# 11.net
KiCad netlist of a schematic drawn in Altium Designer
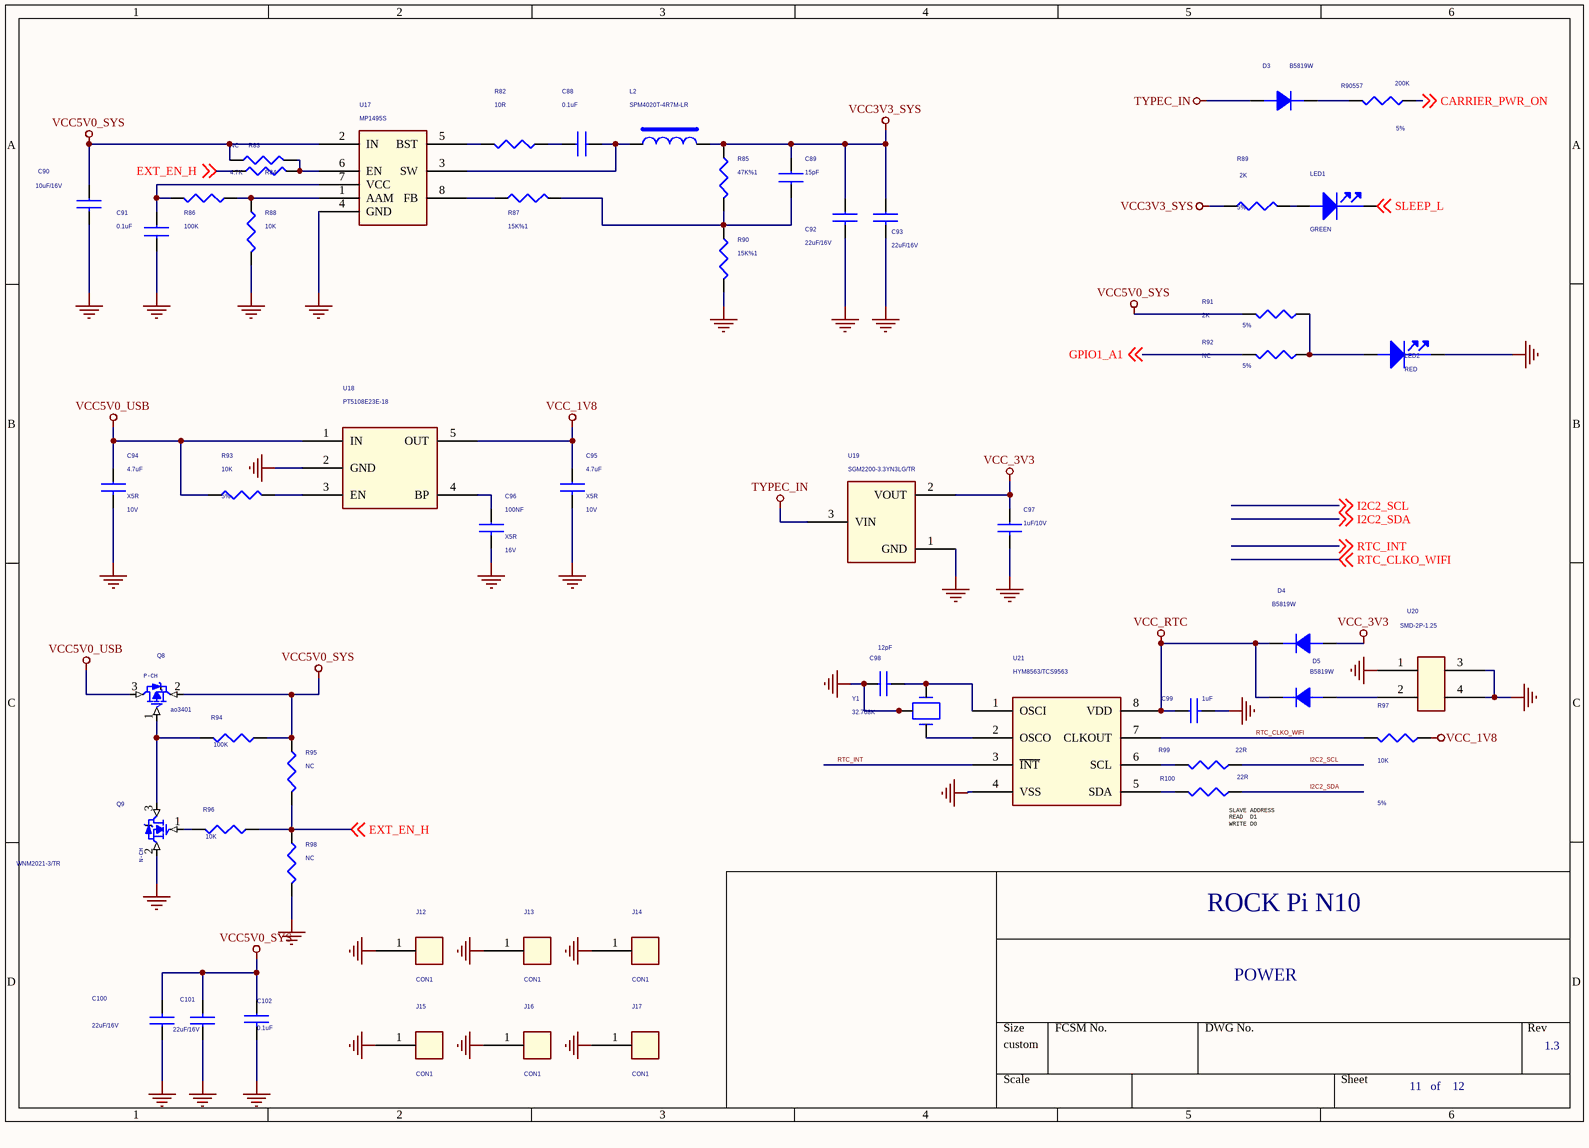
[diagram p0: 11.SchDoc]

(export (version "E")
  (design (tool "Eeschema 10.0.6"))
  (components
    (comp (ref "C88")
      (value "0.1uF")
      (footprint "C0603")
      (description "RoHS CHIP CAP 1uF +10/-10% 16V X5R")
      (libsource (lib "*") (part "CAP NP_Dup3"))
    )
    (comp (ref "C89")
      (value "15pF")
      (footprint "C0603")
      (description "RoHS CHIP CAP 1uF +10/-10% 16V X5R")
      (libsource (lib "*") (part "CAP NP_Dup3"))
    )
    (comp (ref "C90") (value "10uF/16V") (footprint "C0603") (libsource (lib "*") (part "CAP NP_2_Dup1")))
    (comp (ref "C91")
      (value "0.1uF")
      (footprint "C0603")
      (description "RoHS CHIP CAP 1uF +10/-10% 16V X5R")
      (libsource (lib "*") (part "CAP NP_Dup3"))
    )
    (comp (ref "C92") (value "22uF/16V") (footprint "C0805") (libsource (lib "*") (part "CAP NP_2_Dup1")))
    (comp (ref "C93") (value "22uF/16V") (footprint "C0805") (libsource (lib "*") (part "CAP NP_2_Dup1")))
    (comp (ref "C94")
      (value "4.7uF")
      (footprint "C0603")
      (description "cap,4.70uF,+/-10%,10V,X5R,C0603")
      (fields
        (field (name "DIELECTRIC") "X5R")
        (field (name "VOLTAGE") "10V")
        (field (name "MANUFACTURER") "TDK")
        (field (name "TOLERANCE") "10%")
        (field (name "CREATED BY") "JJJ")
      )
      (libsource (lib "*") (part "CAP NP_2"))
    )
    (comp (ref "C95")
      (value "4.7uF")
      (footprint "C0603")
      (description "cap,4.70uF,+/-10%,10V,X5R,C0603")
      (fields
        (field (name "DIELECTRIC") "X5R")
        (field (name "VOLTAGE") "10V")
        (field (name "TOLERANCE") "10%")
        (field (name "MANUFACTURER") "TDK")
        (field (name "CREATED BY") "JJJ")
      )
      (libsource (lib "*") (part "CAP NP_2"))
    )
    (comp (ref "C96")
      (value "100NF")
      (footprint "C0402")
      (description "cap,100.00nF,+/-10%,16V,X5R,C0402")
      (fields
        (field (name "DIELECTRIC") "X5R")
        (field (name "VOLTAGE") "16V")
        (field (name "MANUFACTURER") "TDK")
        (field (name "TOLERANCE") "10%")
        (field (name "CREATED BY") "JJJ")
      )
      (libsource (lib "*") (part "CAP NP_2"))
    )
    (comp (ref "C97")
      (value "1uF/10V")
      (footprint "C0402")
      (description "RoHS CHIP CAP 1uF +10/-10% X5R")
      (libsource (lib "*") (part "CAP NP_Dup1"))
    )
    (comp (ref "C98")
      (value "12pF")
      (footprint "C0402")
      (description "CAP,MLCC,8pF,+/-0.5pF,NPO,6.3V,SMD0402")
      (libsource (lib "*") (part "CAP NP_Dup1"))
    )
    (comp (ref "C99")
      (value "1uF")
      (footprint "C0402")
      (description "RoHS CHIP CAP 1uF +10/-10% X5R")
      (libsource (lib "*") (part "CAP NP_Dup2"))
    )
    (comp (ref "C100") (value "22uF/16V") (footprint "C0805") (libsource (lib "*") (part "CAP NP_4")))
    (comp (ref "C101") (value "22uF/16V") (footprint "C0805") (libsource (lib "*") (part "CAP NP_4")))
    (comp (ref "C102")
      (value "0.1uF")
      (footprint "C0402")
      (description "CAP,MLCC,1nF,+/-10%,X5R,6.3V,SMD0402")
      (libsource (lib "*") (part "CAP NP_Dup1"))
    )
    (comp (ref "D3")
      (value "B5819W")
      (footprint "SOD_123")
      (description "Schottky Barrier，B5819W SOD-123")
      (fields (field (name "MANUFACTURER") "长电") (field (name "CREATED BY") "JJJ"))
      (libsource (lib "*") (part "DIODE"))
    )
    (comp (ref "D4")
      (value "B5819W")
      (footprint "SOD_123")
      (description "Schottky Barrier，B5819W SOD-123")
      (fields (field (name "MANUFACTURER") "长电") (field (name "CREATED BY") "JJJ"))
      (libsource (lib "*") (part "DIODE"))
    )
    (comp (ref "D5")
      (value "B5819W")
      (footprint "SOD_123")
      (description "Schottky Barrier，B5819W SOD-123")
      (fields (field (name "MANUFACTURER") "长电") (field (name "CREATED BY") "JJJ"))
      (libsource (lib "*") (part "DIODE"))
    )
    (comp (ref "J12") (value "CON1") (footprint "H3.8MM") (libsource (lib "*") (part "CON1")))
    (comp (ref "J13") (value "CON1") (footprint "H3.8MM") (libsource (lib "*") (part "CON1")))
    (comp (ref "J14") (value "CON1") (footprint "H3.8MM") (libsource (lib "*") (part "CON1")))
    (comp (ref "J15") (value "CON1") (footprint "H3.8MM") (libsource (lib "*") (part "CON1")))
    (comp (ref "J16") (value "CON1") (footprint "H2.8MM") (libsource (lib "*") (part "CON1")))
    (comp (ref "J17") (value "CON1") (footprint "H2.8MM") (libsource (lib "*") (part "CON1")))
    (comp (ref "L2")
      (value "SPM4020T-4R7M-LR")
      (footprint "IND-4X4")
      (libsource (lib "*") (part "INDUCTORS OF FERRITE_Dup1"))
    )
    (comp (ref "LED1") (value "GREEN") (footprint "LED0603") (libsource (lib "*") (part "LED_0")))
    (comp (ref "LED2")
      (value "RED")
      (footprint "LED0603")
      (description "贴片LED灯，0603，绿色")
      (fields (field (name "CREATED BY") "JJJ"))
      (libsource (lib "*") (part "LED"))
    )
    (comp (ref "Q8") (value "ao3401") (footprint "S0T-23") (libsource (lib "*") (part "P-MOSFET")))
    (comp (ref "Q9") (value "WNM2021-3/TR") (footprint "S0T-23") (libsource (lib "*") (part "N-MOSFET")))
    (comp (ref "R82")
      (value "10R")
      (footprint "R0402")
      (description "RES,thick film,47KOhm,+/-5%,1/16W,SMD0402")
      (libsource (lib "*") (part "RESISTOR_0"))
    )
    (comp (ref "R83")
      (value "NC")
      (footprint "R0402")
      (description "RES,thick film,47KOhm,+/-5%,1/16W,SMD0402")
      (libsource (lib "*") (part "RESISTOR_0"))
    )
    (comp (ref "R84")
      (value "4.7K")
      (footprint "R0402")
      (description "RES,thick film,47KOhm,+/-5%,1/16W,SMD0402")
      (libsource (lib "*") (part "RESISTOR_0"))
    )
    (comp (ref "R85")
      (value "47K%1")
      (footprint "R0402")
      (description "RES,thick film,47KOhm,+/-5%,1/16W,SMD0402")
      (libsource (lib "*") (part "RESISTOR_0"))
    )
    (comp (ref "R86")
      (value "100K")
      (footprint "R0402")
      (description "RES,thick film,47KOhm,+/-5%,1/16W,SMD0402")
      (libsource (lib "*") (part "RESISTOR_0"))
    )
    (comp (ref "R87")
      (value "15K%1")
      (footprint "R0402")
      (description "RES,thick film,47KOhm,+/-5%,1/16W,SMD0402")
      (libsource (lib "*") (part "RESISTOR_0"))
    )
    (comp (ref "R88")
      (value "10K")
      (footprint "R0402")
      (description "RES,thick film,47KOhm,+/-5%,1/16W,SMD0402")
      (libsource (lib "*") (part "RESISTOR_0"))
    )
    (comp (ref "R89")
      (value "2K")
      (footprint "R0402")
      (description "通用厚膜电阻,10K,+/-5%,R0402,1/16W.")
      (fields
        (field (name "TOLERANCE") "5%")
        (field (name "MANUFACTURER") "YAGEO")
        (field (name "CREATED BY") "YTL")
      )
      (libsource (lib "*") (part "RESISTOR_3"))
    )
    (comp (ref "R90")
      (value "15K%1")
      (footprint "R0402")
      (description "RES,thick film,47KOhm,+/-5%,1/16W,SMD0402")
      (libsource (lib "*") (part "RESISTOR_0"))
    )
    (comp (ref "R91")
      (value "2K")
      (footprint "R0402")
      (description "通用厚膜电阻,330R,+/-5%,R0402,1/16W.")
      (fields
        (field (name "TOLERANCE") "5%")
        (field (name "MANUFACTURER") "YAGEO")
        (field (name "CREATED BY") "YTL")
      )
      (libsource (lib "*") (part "RESISTOR_3"))
    )
    (comp (ref "R92")
      (value "NC")
      (footprint "R0402")
      (description "通用厚膜电阻,330R,+/-5%,R0402,1/16W.")
      (fields
        (field (name "TOLERANCE") "5%")
        (field (name "MANUFACTURER") "YAGEO")
        (field (name "CREATED BY") "YTL")
      )
      (libsource (lib "*") (part "RESISTOR_3"))
    )
    (comp (ref "R93")
      (value "10K")
      (footprint "R0402")
      (description "通用厚膜电阻,10K,+/-5%,R0402,1/16W.")
      (fields
        (field (name "TOLERANCE") "5%")
        (field (name "MANUFACTURER") "YAGEO")
        (field (name "CREATED BY") "YTL")
      )
      (libsource (lib "*") (part "RESISTOR_3"))
    )
    (comp (ref "R94")
      (value "100K")
      (footprint "R0402")
      (description "RES,thick film,47KOhm,+/-5%,1/16W,SMD0402")
      (libsource (lib "*") (part "RESISTOR_1"))
    )
    (comp (ref "R95")
      (value "NC")
      (footprint "R0402")
      (description "RES,thick film,47KOhm,+/-5%,1/16W,SMD0402")
      (libsource (lib "*") (part "RESISTOR_0"))
    )
    (comp (ref "R96")
      (value "10K")
      (footprint "R0402")
      (description "RES,thick film,47KOhm,+/-5%,1/16W,SMD0402")
      (libsource (lib "*") (part "RESISTOR_1"))
    )
    (comp (ref "R97")
      (value "10K")
      (footprint "R0402")
      (description "通用厚膜电阻,5K1,+/-5%,R0402,1/16W.")
      (fields
        (field (name "TOLERANCE") "5%")
        (field (name "MANUFACTURER") "YAGEO")
        (field (name "CREATED BY") "YTL")
      )
      (libsource (lib "*") (part "RESISTOR_3"))
    )
    (comp (ref "R98")
      (value "NC")
      (footprint "R0402")
      (description "RES,thick film,47KOhm,+/-5%,1/16W,SMD0402")
      (libsource (lib "*") (part "RESISTOR_0"))
    )
    (comp (ref "R99")
      (value "22R")
      (footprint "R0402")
      (description "通用厚膜电阻,5K1,+/-5%,R0402,1/16W.")
      (fields
        (field (name "TOLERANCE") "5%")
        (field (name "MANUFACTURER") "YAGEO")
        (field (name "CREATED BY") "YTL")
      )
      (libsource (lib "*") (part "RESISTOR_3"))
    )
    (comp (ref "R100")
      (value "22R")
      (footprint "R0402")
      (description "通用厚膜电阻,5K1,+/-5%,R0402,1/16W.")
      (fields
        (field (name "TOLERANCE") "5%")
        (field (name "MANUFACTURER") "YAGEO")
        (field (name "CREATED BY") "YTL")
      )
      (libsource (lib "*") (part "RESISTOR_3"))
    )
    (comp (ref "R90557")
      (value "200K")
      (footprint "R0402")
      (description "通用厚膜电阻,330R,+/-5%,R0402,1/16W.")
      (fields
        (field (name "TOLERANCE") "5%")
        (field (name "MANUFACTURER") "YAGEO")
        (field (name "CREATED BY") "YTL")
      )
      (libsource (lib "*") (part "RESISTOR_3"))
    )
    (comp (ref "U17") (value "MP1495S") (footprint "TSOT_23_8") (libsource (lib "*") (part "BUCK-MP1495")))
    (comp (ref "U18")
      (value "PT5108E23E-18")
      (footprint "SOT25")
      (description "500mA, Low Dropout, Low Noise Ultra-Fast Without Bypass Capacitor CMOS LDO Regulator")
      (fields (field (name "MANUFACTURER") "Richtek（立錡）") (field (name "CREATED BY") "JJJ"))
      (libsource (lib "*") (part "LDO_PT5108"))
    )
    (comp (ref "U19")
      (value "SGM2200-3.3YN3LG/TR")
      (footprint "SOT23")
      (description "High voltage LDO,CE7521MMR,50mA,2.1V output,-0.3V~18V input,SOT23,-40°C~ +85  °C")
      (libsource (lib "*") (part "CE71XXMM"))
    )
    (comp (ref "U20") (value "SMD-2P-1.25") (footprint "SMD-2P-1.25") (libsource (lib "*") (part "CON3_6")))
    (comp (ref "U21")
      (value "HYM8563/TCS9563")
      (footprint "MSOP8")
      (description "RTC IC,CMOS RTC/Calendar,1.0V~5.5V,TSSOP8,-40 ~85℃")
      (libsource (lib "*") (part "LM4990_1"))
    )
    (comp (ref "Y1")
      (value "32.768K")
      (footprint "CRY-MC146")
      (description "OSC,32.768KHz,+/-25ppm,3.3V,12pF,MC146,-20℃~70℃")
      (libsource (lib "*") (part "CRYSTAL_2"))
    )
  )
  (nets
    (net (code "1") (name "CARRIER_PWR_ON") (class "Default")
      (node (ref "R90557") (pin "2") (pinfunction "2_2") (pintype "passive"))
    )
    (net (code "2") (name "EXT_EN_H") (class "Default")
      (node (ref "R84") (pin "2") (pinfunction "2_2") (pintype "passive"))
      (node (ref "R95") (pin "2") (pinfunction "2_2") (pintype "passive"))
      (node (ref "R96") (pin "2") (pinfunction "2_2") (pintype "passive"))
      (node (ref "R98") (pin "1") (pinfunction "1_1") (pintype "passive"))
    )
    (net (code "3") (name "GND") (class "Default")
      (node (ref "C100") (pin "1") (pinfunction "1_1") (pintype "passive"))
      (node (ref "C101") (pin "1") (pinfunction "1_1") (pintype "passive"))
      (node (ref "C102") (pin "2") (pinfunction "2_2") (pintype "passive"))
      (node (ref "C90") (pin "2") (pinfunction "2_2") (pintype "passive"))
      (node (ref "C91") (pin "1") (pinfunction "1_1") (pintype "passive"))
      (node (ref "C92") (pin "2") (pinfunction "2_2") (pintype "passive"))
      (node (ref "C93") (pin "2") (pinfunction "2_2") (pintype "passive"))
      (node (ref "C94") (pin "2") (pinfunction "2_2") (pintype "passive"))
      (node (ref "C95") (pin "2") (pinfunction "2_2") (pintype "passive"))
      (node (ref "C96") (pin "2") (pinfunction "2_2") (pintype "passive"))
      (node (ref "C97") (pin "2") (pinfunction "2_2") (pintype "passive"))
      (node (ref "C98") (pin "1") (pinfunction "1_1") (pintype "passive"))
      (node (ref "C99") (pin "2") (pinfunction "2_2") (pintype "passive"))
      (node (ref "J12") (pin "1") (pinfunction "1_1") (pintype "passive"))
      (node (ref "J13") (pin "1") (pinfunction "1_1") (pintype "passive"))
      (node (ref "J14") (pin "1") (pinfunction "1_1") (pintype "passive"))
      (node (ref "J15") (pin "1") (pinfunction "1_1") (pintype "passive"))
      (node (ref "J16") (pin "1") (pinfunction "1_1") (pintype "passive"))
      (node (ref "J17") (pin "1") (pinfunction "1_1") (pintype "passive"))
      (node (ref "LED2") (pin "2") (pinfunction "CATHODE_2") (pintype "passive"))
      (node (ref "Q9") (pin "2") (pinfunction "S_2") (pintype "input"))
      (node (ref "R88") (pin "2") (pinfunction "2_2") (pintype "passive"))
      (node (ref "R90") (pin "2") (pinfunction "2_2") (pintype "passive"))
      (node (ref "R98") (pin "2") (pinfunction "2_2") (pintype "passive"))
      (node (ref "U17") (pin "4") (pinfunction "GND_4") (pintype "passive"))
      (node (ref "U18") (pin "2") (pinfunction "GND_2") (pintype "passive"))
      (node (ref "U19") (pin "1") (pinfunction "GND_1") (pintype "passive"))
      (node (ref "U20") (pin "1") (pinfunction "1_1") (pintype "passive"))
      (node (ref "U20") (pin "3") (pinfunction "3_3") (pintype "passive"))
      (node (ref "U20") (pin "4") (pinfunction "4_4") (pintype "passive"))
      (node (ref "U21") (pin "4") (pinfunction "VSS_4") (pintype "passive"))
      (node (ref "Y1") (pin "3") (pinfunction "3_3") (pintype "passive"))
      (node (ref "Y1") (pin "4") (pinfunction "4_4") (pintype "passive"))
    )
    (net (code "4") (name "GPIO1_A1") (class "Default")
      (node (ref "R92") (pin "1") (pinfunction "1_1") (pintype "passive"))
    )
    (net (code "5") (name "I2C2_SCL") (class "Default")
      (node (ref "R99") (pin "2") (pinfunction "2_2") (pintype "passive"))
    )
    (net (code "6") (name "I2C2_SDA") (class "Default")
      (node (ref "R100") (pin "2") (pinfunction "2_2") (pintype "passive"))
    )
    (net (code "7") (name "Net-(C88-Pad2)") (class "Default")
      (node (ref "C88") (pin "2") (pinfunction "2_2") (pintype "passive"))
      (node (ref "R82") (pin "1") (pinfunction "1_1") (pintype "passive"))
    )
    (net (code "8") (name "Net-(C89-Pad1)") (class "Default")
      (node (ref "C89") (pin "1") (pinfunction "1_1") (pintype "passive"))
      (node (ref "R85") (pin "2") (pinfunction "2_2") (pintype "passive"))
      (node (ref "R87") (pin "2") (pinfunction "2_2") (pintype "passive"))
      (node (ref "R90") (pin "1") (pinfunction "1_1") (pintype "passive"))
    )
    (net (code "9") (name "Net-(D3-K)") (class "Default")
      (node (ref "D3") (pin "2") (pinfunction "K_2") (pintype "passive"))
      (node (ref "R90557") (pin "1") (pinfunction "1_1") (pintype "passive"))
    )
    (net (code "10") (name "Net-(D5-A)") (class "Default")
      (node (ref "D5") (pin "1") (pinfunction "A_1") (pintype "passive"))
      (node (ref "U20") (pin "2") (pinfunction "2_2") (pintype "passive"))
    )
    (net (code "11") (name "Net-(LED1-ANODE)") (class "Default")
      (node (ref "LED1") (pin "1") (pinfunction "ANODE_1") (pintype "passive"))
      (node (ref "R89") (pin "2") (pinfunction "2_2") (pintype "passive"))
    )
    (net (code "12") (name "Net-(LED2-ANODE)") (class "Default")
      (node (ref "LED2") (pin "1") (pinfunction "ANODE_1") (pintype "passive"))
      (node (ref "R91") (pin "2") (pinfunction "2_2") (pintype "passive"))
      (node (ref "R92") (pin "2") (pinfunction "2_2") (pintype "passive"))
    )
    (net (code "13") (name "Net-(Q8-G)") (class "Default")
      (node (ref "Q8") (pin "1") (pinfunction "G_1") (pintype "input"))
      (node (ref "Q9") (pin "3") (pinfunction "D_3") (pintype "input"))
      (node (ref "R94") (pin "1") (pinfunction "1_1") (pintype "passive"))
    )
    (net (code "14") (name "Net-(Q9-G)") (class "Default")
      (node (ref "Q9") (pin "1") (pinfunction "G_1") (pintype "input"))
      (node (ref "R96") (pin "1") (pinfunction "1_1") (pintype "passive"))
    )
    (net (code "15") (name "Net-(U17-AAM)") (class "Default")
      (node (ref "R86") (pin "1") (pinfunction "1_1") (pintype "passive"))
      (node (ref "R88") (pin "1") (pinfunction "1_1") (pintype "passive"))
      (node (ref "U17") (pin "1") (pinfunction "AAM_1") (pintype "passive"))
    )
    (net (code "16") (name "Net-(U17-BST)") (class "Default")
      (node (ref "R82") (pin "2") (pinfunction "2_2") (pintype "passive"))
      (node (ref "U17") (pin "5") (pinfunction "BST_5") (pintype "passive"))
    )
    (net (code "17") (name "Net-(U17-EN)") (class "Default")
      (node (ref "R83") (pin "1") (pinfunction "1_1") (pintype "passive"))
      (node (ref "R84") (pin "1") (pinfunction "1_1") (pintype "passive"))
      (node (ref "U17") (pin "6") (pinfunction "EN_6") (pintype "passive"))
    )
    (net (code "18") (name "Net-(U17-FB)") (class "Default")
      (node (ref "R87") (pin "1") (pinfunction "1_1") (pintype "passive"))
      (node (ref "U17") (pin "8") (pinfunction "FB_8") (pintype "passive"))
    )
    (net (code "19") (name "Net-(U17-SW)") (class "Default")
      (node (ref "C88") (pin "1") (pinfunction "1_1") (pintype "passive"))
      (node (ref "L2") (pin "1") (pinfunction "1_1") (pintype "passive"))
      (node (ref "U17") (pin "3") (pinfunction "SW_3") (pintype "passive"))
    )
    (net (code "20") (name "Net-(U17-VCC)") (class "Default")
      (node (ref "C91") (pin "2") (pinfunction "2_2") (pintype "passive"))
      (node (ref "R86") (pin "2") (pinfunction "2_2") (pintype "passive"))
      (node (ref "U17") (pin "7") (pinfunction "VCC_7") (pintype "passive"))
    )
    (net (code "21") (name "Net-(U18-BP)") (class "Default")
      (node (ref "C96") (pin "1") (pinfunction "1_1") (pintype "passive"))
      (node (ref "U18") (pin "4") (pinfunction "BP_4") (pintype "passive"))
    )
    (net (code "22") (name "Net-(U18-EN)") (class "Default")
      (node (ref "R93") (pin "2") (pinfunction "2_2") (pintype "passive"))
      (node (ref "U18") (pin "3") (pinfunction "EN_3") (pintype "passive"))
    )
    (net (code "23") (name "Net-(U21-OSCI)") (class "Default")
      (node (ref "C98") (pin "2") (pinfunction "2_2") (pintype "passive"))
      (node (ref "U21") (pin "1") (pinfunction "OSCI_1") (pintype "passive"))
      (node (ref "Y1") (pin "1") (pinfunction "1_1") (pintype "passive"))
    )
    (net (code "24") (name "Net-(U21-OSCO)") (class "Default")
      (node (ref "U21") (pin "2") (pinfunction "OSCO_2") (pintype "passive"))
      (node (ref "Y1") (pin "2") (pinfunction "2_2") (pintype "passive"))
    )
    (net (code "25") (name "Net-(U21-SCL)") (class "Default")
      (node (ref "R99") (pin "1") (pinfunction "1_1") (pintype "passive"))
      (node (ref "U21") (pin "6") (pinfunction "SCL_6") (pintype "passive"))
    )
    (net (code "26") (name "Net-(U21-SDA)") (class "Default")
      (node (ref "R100") (pin "1") (pinfunction "1_1") (pintype "passive"))
      (node (ref "U21") (pin "5") (pinfunction "SDA_5") (pintype "passive"))
    )
    (net (code "27") (name "RTC_CLKO_WIFI") (class "Default")
      (node (ref "R97") (pin "1") (pinfunction "1_1") (pintype "passive"))
      (node (ref "U21") (pin "7") (pinfunction "CLKOUT_7") (pintype "passive"))
    )
    (net (code "28") (name "RTC_INT") (class "Default")
      (node (ref "U21") (pin "3") (pinfunction "~{INT}_3") (pintype "passive"))
    )
    (net (code "29") (name "SLEEP_L") (class "Default")
      (node (ref "LED1") (pin "2") (pinfunction "CATHODE_2") (pintype "passive"))
    )
    (net (code "30") (name "TYPEC_IN") (class "Default")
      (node (ref "D3") (pin "1") (pinfunction "A_1") (pintype "passive"))
      (node (ref "U19") (pin "3") (pinfunction "VIN_3") (pintype "passive"))
    )
    (net (code "31") (name "VCC3V3_SYS") (class "Default")
      (node (ref "C89") (pin "2") (pinfunction "2_2") (pintype "passive"))
      (node (ref "C92") (pin "1") (pinfunction "1_1") (pintype "passive"))
      (node (ref "C93") (pin "1") (pinfunction "1_1") (pintype "passive"))
      (node (ref "L2") (pin "2") (pinfunction "2_2") (pintype "passive"))
      (node (ref "R85") (pin "1") (pinfunction "1_1") (pintype "passive"))
      (node (ref "R89") (pin "1") (pinfunction "1_1") (pintype "passive"))
    )
    (net (code "32") (name "VCC5V0_SYS") (class "Default")
      (node (ref "C100") (pin "2") (pinfunction "2_2") (pintype "passive"))
      (node (ref "C101") (pin "2") (pinfunction "2_2") (pintype "passive"))
      (node (ref "C102") (pin "1") (pinfunction "1_1") (pintype "passive"))
      (node (ref "C90") (pin "1") (pinfunction "1_1") (pintype "passive"))
      (node (ref "Q8") (pin "2") (pinfunction "S_2") (pintype "input"))
      (node (ref "R83") (pin "2") (pinfunction "2_2") (pintype "passive"))
      (node (ref "R91") (pin "1") (pinfunction "1_1") (pintype "passive"))
      (node (ref "R94") (pin "2") (pinfunction "2_2") (pintype "passive"))
      (node (ref "R95") (pin "1") (pinfunction "1_1") (pintype "passive"))
      (node (ref "U17") (pin "2") (pinfunction "IN_2") (pintype "passive"))
    )
    (net (code "33") (name "VCC5V0_USB") (class "Default")
      (node (ref "C94") (pin "1") (pinfunction "1_1") (pintype "passive"))
      (node (ref "Q8") (pin "3") (pinfunction "D_3") (pintype "input"))
      (node (ref "R93") (pin "1") (pinfunction "1_1") (pintype "passive"))
      (node (ref "U18") (pin "1") (pinfunction "IN_1") (pintype "passive"))
    )
    (net (code "34") (name "VCC_1V8") (class "Default")
      (node (ref "C95") (pin "1") (pinfunction "1_1") (pintype "passive"))
      (node (ref "R97") (pin "2") (pinfunction "2_2") (pintype "passive"))
      (node (ref "U18") (pin "5") (pinfunction "OUT_5") (pintype "passive"))
    )
    (net (code "35") (name "VCC_3V3") (class "Default")
      (node (ref "C97") (pin "1") (pinfunction "1_1") (pintype "passive"))
      (node (ref "D4") (pin "1") (pinfunction "A_1") (pintype "passive"))
      (node (ref "U19") (pin "2") (pinfunction "VOUT_2") (pintype "passive"))
    )
    (net (code "36") (name "VCC_RTC") (class "Default")
      (node (ref "C99") (pin "1") (pinfunction "1_1") (pintype "passive"))
      (node (ref "D4") (pin "2") (pinfunction "K_2") (pintype "passive"))
      (node (ref "D5") (pin "2") (pinfunction "K_2") (pintype "passive"))
      (node (ref "U21") (pin "8") (pinfunction "VDD_8") (pintype "passive"))
    )
  )
)
